# UTS_RaceCounter.net
KiCad netlist of a schematic drawn in EAGLE
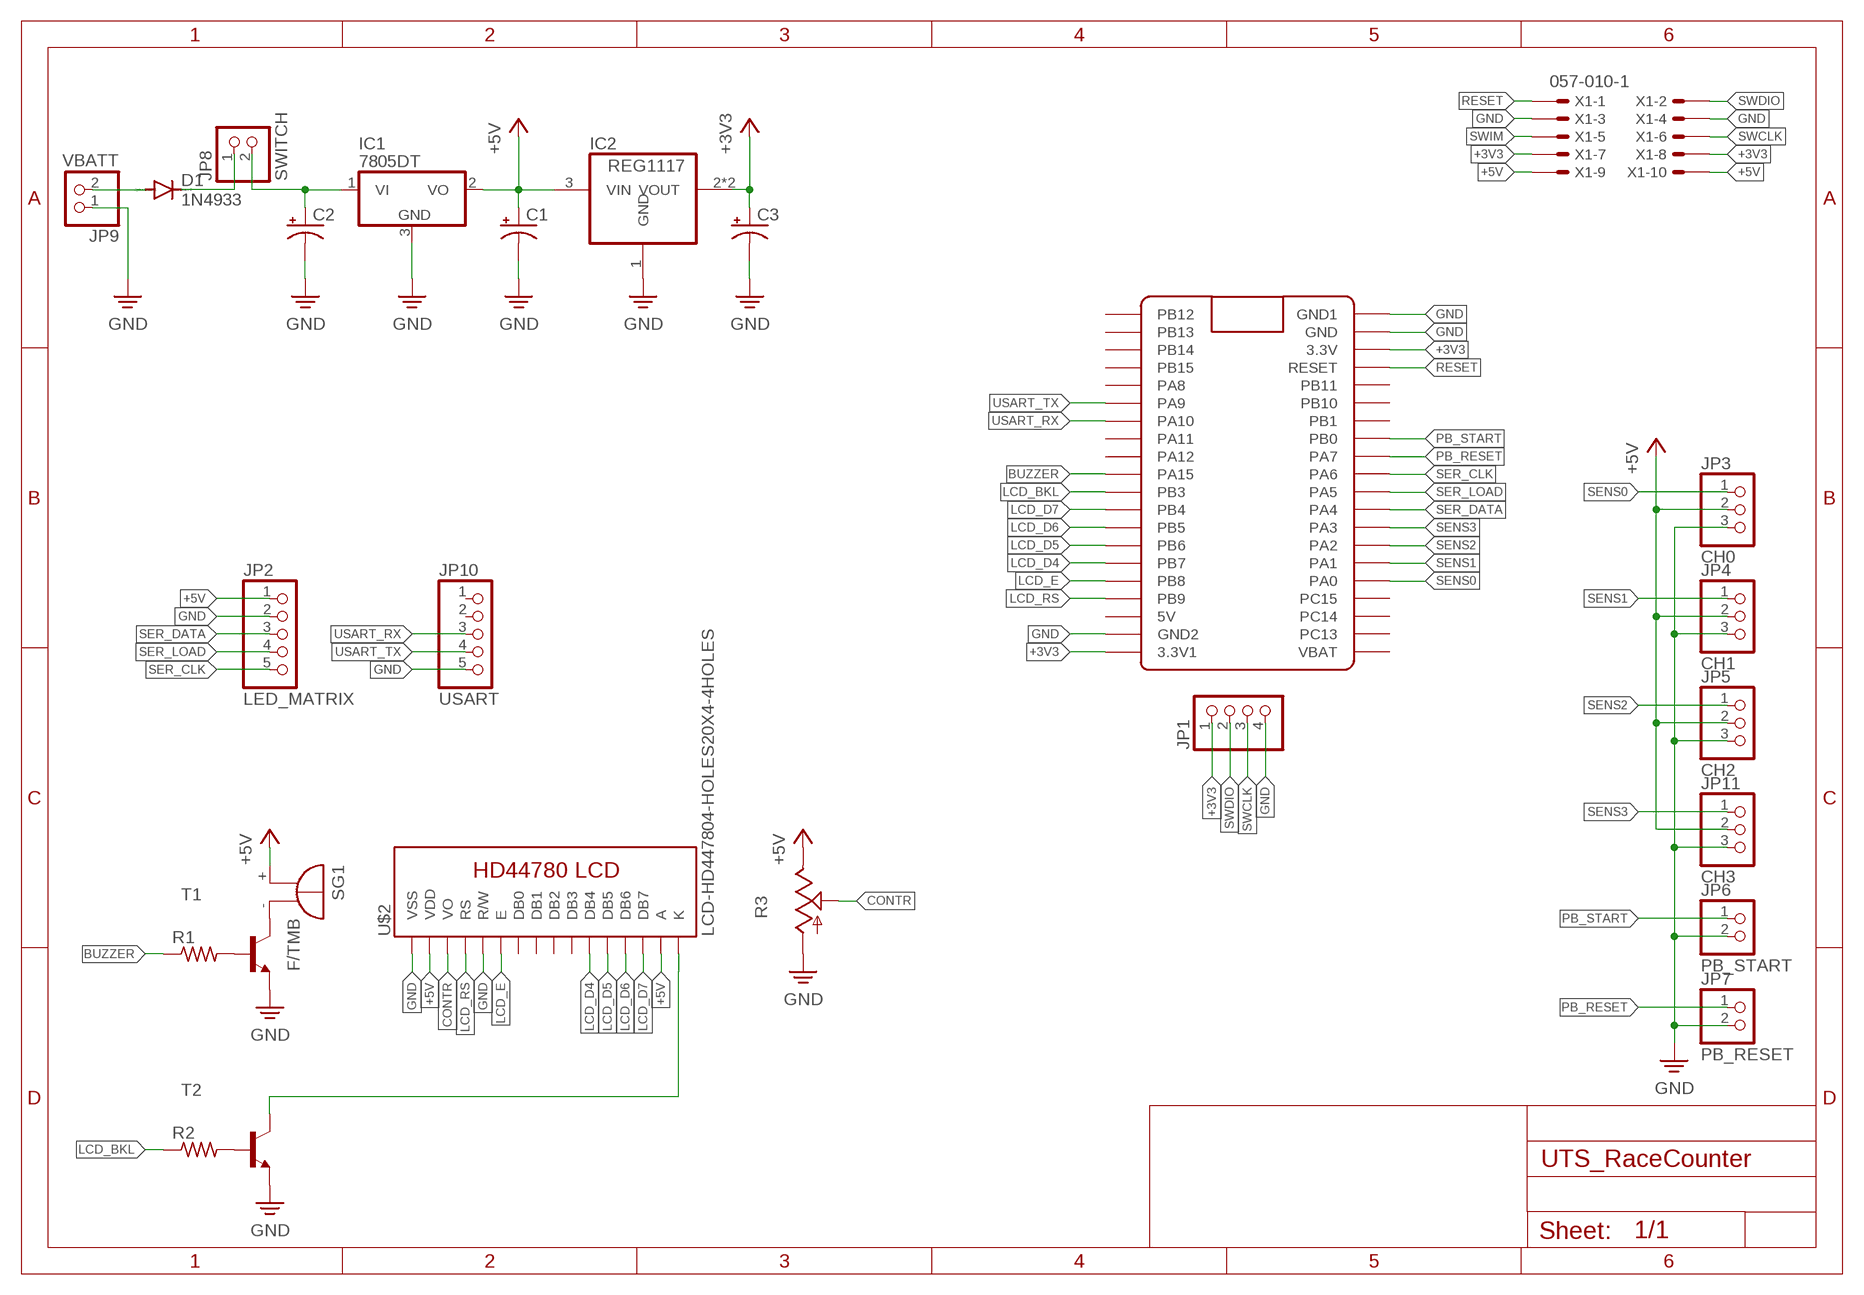
[diagram p0: schematic, sheet 1]

(export (version "E")
  (design (tool "Eeschema 10.0.6"))
  (components
    (comp (ref "C1")
      (value "CPOL-USE2.5-6")
      (footprint "eagle-import:E2,5-6")
      (libsource (lib "eagle-import") (part "CPOL-USE2.5-6"))
    )
    (comp (ref "C2")
      (value "CPOL-USE2.5-6")
      (footprint "eagle-import:E2,5-6")
      (libsource (lib "eagle-import") (part "CPOL-USE2.5-6"))
    )
    (comp (ref "C3")
      (value "CPOL-USE2.5-6")
      (footprint "eagle-import:E2,5-6")
      (libsource (lib "eagle-import") (part "CPOL-USE2.5-6"))
    )
    (comp (ref "D1")
      (value "1N4933")
      (footprint "eagle-import:DO41-10")
      (libsource (lib "eagle-import") (part "1N4933"))
    )
    (comp (ref "IC1")
      (value "7805DT")
      (footprint "eagle-import:TO252")
      (libsource (lib "eagle-import") (part "78DT05"))
    )
    (comp (ref "IC2")
      (value "REG1117")
      (footprint "eagle-import:SOT223")
      (libsource (lib "eagle-import") (part "REG1117"))
    )
    (comp (ref "JP1")
      (value "PINHD-1X4")
      (footprint "eagle-import:1X04")
      (libsource (lib "eagle-import") (part "PINHD-1X4"))
    )
    (comp (ref "JP2")
      (value "LED_MATRIX")
      (footprint "eagle-import:1X05")
      (libsource (lib "eagle-import") (part "PINHD-1X5"))
    )
    (comp (ref "JP3")
      (value "CH0")
      (footprint "eagle-import:1X03")
      (libsource (lib "eagle-import") (part "PINHD-1X3"))
    )
    (comp (ref "JP4")
      (value "CH1")
      (footprint "eagle-import:1X03")
      (libsource (lib "eagle-import") (part "PINHD-1X3"))
    )
    (comp (ref "JP5")
      (value "CH2")
      (footprint "eagle-import:1X03")
      (libsource (lib "eagle-import") (part "PINHD-1X3"))
    )
    (comp (ref "JP6")
      (value "PB_START")
      (footprint "eagle-import:1X02")
      (libsource (lib "eagle-import") (part "PINHD-1X2"))
    )
    (comp (ref "JP7")
      (value "PB_RESET")
      (footprint "eagle-import:1X02")
      (libsource (lib "eagle-import") (part "PINHD-1X2"))
    )
    (comp (ref "JP8")
      (value "SWITCH")
      (footprint "eagle-import:1X02")
      (libsource (lib "eagle-import") (part "PINHD-1X2"))
    )
    (comp (ref "JP9")
      (value "VBATT")
      (footprint "eagle-import:1X02")
      (libsource (lib "eagle-import") (part "PINHD-1X2"))
    )
    (comp (ref "JP10")
      (value "USART")
      (footprint "eagle-import:1X05")
      (libsource (lib "eagle-import") (part "PINHD-1X5"))
    )
    (comp (ref "JP11")
      (value "CH3")
      (footprint "eagle-import:1X03")
      (libsource (lib "eagle-import") (part "PINHD-1X3"))
    )
    (comp (ref "R1")
      (value "R-US_0204/7")
      (footprint "eagle-import:0204_7")
      (libsource (lib "eagle-import") (part "R-US_0204/7"))
    )
    (comp (ref "R2")
      (value "R-US_0204/7")
      (footprint "eagle-import:0204_7")
      (libsource (lib "eagle-import") (part "R-US_0204/7"))
    )
    (comp (ref "R3")
      (value "TRIM_US-CA6V")
      (footprint "eagle-import:CA6V")
      (libsource (lib "eagle-import") (part "TRIM_US-CA6V"))
    )
    (comp (ref "SG1")
      (value "F/TMB")
      (footprint "eagle-import:F_TMB")
      (libsource (lib "eagle-import") (part "F/TMB"))
    )
    (comp (ref "T1")
      (value "BC167-NPN-TO92-ECB")
      (footprint "eagle-import:TO92-ECB")
      (libsource (lib "eagle-import") (part "-NPN-TO92-ECBBC167"))
    )
    (comp (ref "T2")
      (value "BC167-NPN-TO92-ECB")
      (footprint "eagle-import:TO92-ECB")
      (libsource (lib "eagle-import") (part "-NPN-TO92-ECBBC167"))
    )
    (comp (ref "U$1")
      (value "BLUE_PILL")
      (footprint "eagle-import:BLUE_PILL")
      (libsource (lib "eagle-import") (part "BLUE_PILL"))
    )
    (comp (ref "U$2")
      (value "LCD-HD447804-HOLES20X4-4HOLES")
      (footprint "eagle-import:LCD-20X4-4HOLES")
      (libsource (lib "eagle-import") (part "LCD-HD4478020X4-4HOLES4-HOLES"))
    )
    (comp (ref "X1")
      (value "057-010-1")
      (footprint "eagle-import:057-010-1")
      (libsource (lib "eagle-import") (part "057-010-1"))
    )
  )
  (nets
    (net (code "1") (name "+3V3") (class "Default")
      (node (ref "C3") (pin "+") (pinfunction "+_+") (pintype "passive"))
      (node (ref "IC2") (pin "2") (pinfunction "VOUT_2") (pintype "output"))
      (node (ref "IC2") (pin "4") (pinfunction "VOUT_4") (pintype "output"))
      (node (ref "JP1") (pin "1") (pinfunction "1_1") (pintype "passive"))
      (node (ref "U$1") (pin "P$20") (pinfunction "3.3V1_P$20") (pintype "bidirectional"))
      (node (ref "U$1") (pin "P$23") (pinfunction "3.3V_P$23") (pintype "bidirectional"))
      (node (ref "X1") (pin "7") (pinfunction "S_7") (pintype "passive"))
      (node (ref "X1") (pin "8") (pinfunction "S_8") (pintype "passive"))
    )
    (net (code "2") (name "+5V") (class "Default")
      (node (ref "C1") (pin "+") (pinfunction "+_+") (pintype "passive"))
      (node (ref "IC1") (pin "2") (pinfunction "VO_2") (pintype "passive"))
      (node (ref "IC2") (pin "3") (pinfunction "VIN_3") (pintype "input"))
      (node (ref "JP11") (pin "2") (pinfunction "2_2") (pintype "passive"))
      (node (ref "JP2") (pin "1") (pinfunction "1_1") (pintype "passive"))
      (node (ref "JP3") (pin "2") (pinfunction "2_2") (pintype "passive"))
      (node (ref "JP4") (pin "2") (pinfunction "2_2") (pintype "passive"))
      (node (ref "JP5") (pin "2") (pinfunction "2_2") (pintype "passive"))
      (node (ref "R3") (pin "E") (pinfunction "E_E") (pintype "passive"))
      (node (ref "SG1") (pin "+") (pinfunction "+_+") (pintype "passive"))
      (node (ref "U$2") (pin "P$15") (pinfunction "A_P$15") (pintype "power_in"))
      (node (ref "U$2") (pin "P$2") (pinfunction "VDD_P$2") (pintype "power_in"))
      (node (ref "X1") (pin "10") (pinfunction "S_10") (pintype "passive"))
      (node (ref "X1") (pin "9") (pinfunction "S_9") (pintype "passive"))
    )
    (net (code "3") (name "BUZZER") (class "Default")
      (node (ref "R1") (pin "1") (pinfunction "1_1") (pintype "passive"))
      (node (ref "U$1") (pin "P$10") (pinfunction "PA15_P$10") (pintype "bidirectional"))
    )
    (net (code "4") (name "CONTR") (class "Default")
      (node (ref "R3") (pin "S") (pinfunction "S_S") (pintype "passive"))
      (node (ref "U$2") (pin "P$3") (pinfunction "VO_P$3") (pintype "bidirectional"))
    )
    (net (code "5") (name "GND") (class "Default")
      (node (ref "C1") (pin "-") (pinfunction "-_-") (pintype "passive"))
      (node (ref "C2") (pin "-") (pinfunction "-_-") (pintype "passive"))
      (node (ref "C3") (pin "-") (pinfunction "-_-") (pintype "passive"))
      (node (ref "IC1") (pin "3") (pinfunction "GND_3") (pintype "passive"))
      (node (ref "IC2") (pin "1") (pinfunction "GND_1") (pintype "power_in"))
      (node (ref "JP1") (pin "4") (pinfunction "4_4") (pintype "passive"))
      (node (ref "JP10") (pin "5") (pinfunction "5_5") (pintype "passive"))
      (node (ref "JP11") (pin "3") (pinfunction "3_3") (pintype "passive"))
      (node (ref "JP2") (pin "2") (pinfunction "2_2") (pintype "passive"))
      (node (ref "JP3") (pin "3") (pinfunction "3_3") (pintype "passive"))
      (node (ref "JP4") (pin "3") (pinfunction "3_3") (pintype "passive"))
      (node (ref "JP5") (pin "3") (pinfunction "3_3") (pintype "passive"))
      (node (ref "JP6") (pin "2") (pinfunction "2_2") (pintype "passive"))
      (node (ref "JP7") (pin "2") (pinfunction "2_2") (pintype "passive"))
      (node (ref "JP9") (pin "1") (pinfunction "1_1") (pintype "passive"))
      (node (ref "R3") (pin "A") (pinfunction "A_A") (pintype "passive"))
      (node (ref "T1") (pin "E") (pinfunction "E_E") (pintype "passive"))
      (node (ref "T2") (pin "E") (pinfunction "E_E") (pintype "passive"))
      (node (ref "U$1") (pin "P$19") (pinfunction "GND2_P$19") (pintype "bidirectional"))
      (node (ref "U$1") (pin "P$21") (pinfunction "GND1_P$21") (pintype "power_in"))
      (node (ref "U$1") (pin "P$22") (pinfunction "GND_P$22") (pintype "bidirectional"))
      (node (ref "U$2") (pin "P$1") (pinfunction "VSS_P$1") (pintype "power_in"))
      (node (ref "U$2") (pin "P$5") (pinfunction "R/W_P$5") (pintype "input"))
      (node (ref "X1") (pin "3") (pinfunction "S_3") (pintype "passive"))
      (node (ref "X1") (pin "4") (pinfunction "S_4") (pintype "passive"))
    )
    (net (code "6") (name "LCD_BKL") (class "Default")
      (node (ref "R2") (pin "1") (pinfunction "1_1") (pintype "passive"))
      (node (ref "U$1") (pin "P$11") (pinfunction "PB3_P$11") (pintype "bidirectional"))
    )
    (net (code "7") (name "LCD_D4") (class "Default")
      (node (ref "U$1") (pin "P$15") (pinfunction "PB7_P$15") (pintype "bidirectional"))
      (node (ref "U$2") (pin "P$11") (pinfunction "DB4_P$11") (pintype "bidirectional"))
    )
    (net (code "8") (name "LCD_D5") (class "Default")
      (node (ref "U$1") (pin "P$14") (pinfunction "PB6_P$14") (pintype "bidirectional"))
      (node (ref "U$2") (pin "P$12") (pinfunction "DB5_P$12") (pintype "bidirectional"))
    )
    (net (code "9") (name "LCD_D6") (class "Default")
      (node (ref "U$1") (pin "P$13") (pinfunction "PB5_P$13") (pintype "bidirectional"))
      (node (ref "U$2") (pin "P$13") (pinfunction "DB6_P$13") (pintype "bidirectional"))
    )
    (net (code "10") (name "LCD_D7") (class "Default")
      (node (ref "U$1") (pin "P$12") (pinfunction "PB4_P$12") (pintype "bidirectional"))
      (node (ref "U$2") (pin "P$14") (pinfunction "DB7_P$14") (pintype "bidirectional"))
    )
    (net (code "11") (name "LCD_E") (class "Default")
      (node (ref "U$1") (pin "P$16") (pinfunction "PB8_P$16") (pintype "bidirectional"))
      (node (ref "U$2") (pin "P$6") (pinfunction "E_P$6") (pintype "input"))
    )
    (net (code "12") (name "LCD_RS") (class "Default")
      (node (ref "U$1") (pin "P$17") (pinfunction "PB9_P$17") (pintype "bidirectional"))
      (node (ref "U$2") (pin "P$4") (pinfunction "RS_P$4") (pintype "input"))
    )
    (net (code "13") (name "Net-(D1-PadA)") (class "Default")
      (node (ref "D1") (pin "A") (pinfunction "A_A") (pintype "passive"))
      (node (ref "JP9") (pin "2") (pinfunction "2_2") (pintype "passive"))
    )
    (net (code "14") (name "Net-(D1-PadC)") (class "Default")
      (node (ref "D1") (pin "C") (pinfunction "C_C") (pintype "passive"))
      (node (ref "JP8") (pin "1") (pinfunction "1_1") (pintype "passive"))
    )
    (net (code "15") (name "Net-(IC1-VI)") (class "Default")
      (node (ref "C2") (pin "+") (pinfunction "+_+") (pintype "passive"))
      (node (ref "IC1") (pin "1") (pinfunction "VI_1") (pintype "input"))
      (node (ref "JP8") (pin "2") (pinfunction "2_2") (pintype "passive"))
    )
    (net (code "16") (name "Net-(R1-Pad2)") (class "Default")
      (node (ref "R1") (pin "2") (pinfunction "2_2") (pintype "passive"))
      (node (ref "T1") (pin "B") (pinfunction "B_B") (pintype "passive"))
    )
    (net (code "17") (name "Net-(R2-Pad2)") (class "Default")
      (node (ref "R2") (pin "2") (pinfunction "2_2") (pintype "passive"))
      (node (ref "T2") (pin "B") (pinfunction "B_B") (pintype "passive"))
    )
    (net (code "18") (name "Net-(SG1-Pad-)") (class "Default")
      (node (ref "SG1") (pin "-") (pinfunction "-_-") (pintype "passive"))
      (node (ref "T1") (pin "C") (pinfunction "C_C") (pintype "passive"))
    )
    (net (code "19") (name "Net-(U$2-K)") (class "Default")
      (node (ref "T2") (pin "C") (pinfunction "C_C") (pintype "passive"))
      (node (ref "U$2") (pin "P$16") (pinfunction "K_P$16") (pintype "power_in"))
    )
    (net (code "20") (name "PB_RESET") (class "Default")
      (node (ref "JP7") (pin "1") (pinfunction "1_1") (pintype "passive"))
      (node (ref "U$1") (pin "P$29") (pinfunction "PA7_P$29") (pintype "bidirectional"))
    )
    (net (code "21") (name "PB_START") (class "Default")
      (node (ref "JP6") (pin "1") (pinfunction "1_1") (pintype "passive"))
      (node (ref "U$1") (pin "P$28") (pinfunction "PB0_P$28") (pintype "bidirectional"))
    )
    (net (code "22") (name "RESET") (class "Default")
      (node (ref "U$1") (pin "P$24") (pinfunction "RESET_P$24") (pintype "bidirectional"))
      (node (ref "X1") (pin "1") (pinfunction "S_1") (pintype "passive"))
    )
    (net (code "23") (name "SENS0") (class "Default")
      (node (ref "JP3") (pin "1") (pinfunction "1_1") (pintype "passive"))
      (node (ref "U$1") (pin "P$36") (pinfunction "PA0_P$36") (pintype "bidirectional"))
    )
    (net (code "24") (name "SENS1") (class "Default")
      (node (ref "JP4") (pin "1") (pinfunction "1_1") (pintype "passive"))
      (node (ref "U$1") (pin "P$35") (pinfunction "PA1_P$35") (pintype "bidirectional"))
    )
    (net (code "25") (name "SENS2") (class "Default")
      (node (ref "JP5") (pin "1") (pinfunction "1_1") (pintype "passive"))
      (node (ref "U$1") (pin "P$34") (pinfunction "PA2_P$34") (pintype "bidirectional"))
    )
    (net (code "26") (name "SENS3") (class "Default")
      (node (ref "JP11") (pin "1") (pinfunction "1_1") (pintype "passive"))
      (node (ref "U$1") (pin "P$33") (pinfunction "PA3_P$33") (pintype "bidirectional"))
    )
    (net (code "27") (name "SER_CLK") (class "Default")
      (node (ref "JP2") (pin "5") (pinfunction "5_5") (pintype "passive"))
      (node (ref "U$1") (pin "P$30") (pinfunction "PA6_P$30") (pintype "bidirectional"))
    )
    (net (code "28") (name "SER_DATA") (class "Default")
      (node (ref "JP2") (pin "3") (pinfunction "3_3") (pintype "passive"))
      (node (ref "U$1") (pin "P$32") (pinfunction "PA4_P$32") (pintype "bidirectional"))
    )
    (net (code "29") (name "SER_LOAD") (class "Default")
      (node (ref "JP2") (pin "4") (pinfunction "4_4") (pintype "passive"))
      (node (ref "U$1") (pin "P$31") (pinfunction "PA5_P$31") (pintype "bidirectional"))
    )
    (net (code "30") (name "SWCLK") (class "Default")
      (node (ref "JP1") (pin "3") (pinfunction "3_3") (pintype "passive"))
      (node (ref "X1") (pin "6") (pinfunction "S_6") (pintype "passive"))
    )
    (net (code "31") (name "SWDIO") (class "Default")
      (node (ref "JP1") (pin "2") (pinfunction "2_2") (pintype "passive"))
      (node (ref "X1") (pin "2") (pinfunction "S_2") (pintype "passive"))
    )
    (net (code "32") (name "SWIM") (class "Default")
      (node (ref "X1") (pin "5") (pinfunction "S_5") (pintype "passive"))
    )
    (net (code "33") (name "USART_RX") (class "Default")
      (node (ref "JP10") (pin "3") (pinfunction "3_3") (pintype "passive"))
      (node (ref "U$1") (pin "P$7") (pinfunction "PA10_P$7") (pintype "bidirectional"))
    )
    (net (code "34") (name "USART_TX") (class "Default")
      (node (ref "JP10") (pin "4") (pinfunction "4_4") (pintype "passive"))
      (node (ref "U$1") (pin "P$6") (pinfunction "PA9_P$6") (pintype "bidirectional"))
    )
    (net (code "35") (name "unconnected-(JP10-Pad1)") (class "Default")
      (node (ref "JP10") (pin "1") (pinfunction "1_1") (pintype "passive"))
    )
    (net (code "36") (name "unconnected-(JP10-Pad2)") (class "Default")
      (node (ref "JP10") (pin "2") (pinfunction "2_2") (pintype "passive"))
    )
    (net (code "37") (name "unconnected-(U$1-5V-PadP$18)") (class "Default")
      (node (ref "U$1") (pin "P$18") (pinfunction "5V_P$18") (pintype "bidirectional"))
    )
    (net (code "38") (name "unconnected-(U$1-PA8-PadP$5)") (class "Default")
      (node (ref "U$1") (pin "P$5") (pinfunction "PA8_P$5") (pintype "bidirectional"))
    )
    (net (code "39") (name "unconnected-(U$1-PA11-PadP$8)") (class "Default")
      (node (ref "U$1") (pin "P$8") (pinfunction "PA11_P$8") (pintype "bidirectional"))
    )
    (net (code "40") (name "unconnected-(U$1-PA12-PadP$9)") (class "Default")
      (node (ref "U$1") (pin "P$9") (pinfunction "PA12_P$9") (pintype "bidirectional"))
    )
    (net (code "41") (name "unconnected-(U$1-PB1-PadP$27)") (class "Default")
      (node (ref "U$1") (pin "P$27") (pinfunction "PB1_P$27") (pintype "bidirectional"))
    )
    (net (code "42") (name "unconnected-(U$1-PB10-PadP$26)") (class "Default")
      (node (ref "U$1") (pin "P$26") (pinfunction "PB10_P$26") (pintype "bidirectional"))
    )
    (net (code "43") (name "unconnected-(U$1-PB11-PadP$25)") (class "Default")
      (node (ref "U$1") (pin "P$25") (pinfunction "PB11_P$25") (pintype "bidirectional"))
    )
    (net (code "44") (name "unconnected-(U$1-PB12-PadP$1)") (class "Default")
      (node (ref "U$1") (pin "P$1") (pinfunction "PB12_P$1") (pintype "bidirectional"))
    )
    (net (code "45") (name "unconnected-(U$1-PB13-PadP$2)") (class "Default")
      (node (ref "U$1") (pin "P$2") (pinfunction "PB13_P$2") (pintype "bidirectional"))
    )
    (net (code "46") (name "unconnected-(U$1-PB14-PadP$3)") (class "Default")
      (node (ref "U$1") (pin "P$3") (pinfunction "PB14_P$3") (pintype "bidirectional"))
    )
    (net (code "47") (name "unconnected-(U$1-PB15-PadP$4)") (class "Default")
      (node (ref "U$1") (pin "P$4") (pinfunction "PB15_P$4") (pintype "bidirectional"))
    )
    (net (code "48") (name "unconnected-(U$1-PC13-PadP$39)") (class "Default")
      (node (ref "U$1") (pin "P$39") (pinfunction "PC13_P$39") (pintype "bidirectional"))
    )
    (net (code "49") (name "unconnected-(U$1-PC14-PadP$38)") (class "Default")
      (node (ref "U$1") (pin "P$38") (pinfunction "PC14_P$38") (pintype "bidirectional"))
    )
    (net (code "50") (name "unconnected-(U$1-PC15-PadP$37)") (class "Default")
      (node (ref "U$1") (pin "P$37") (pinfunction "PC15_P$37") (pintype "bidirectional"))
    )
    (net (code "51") (name "unconnected-(U$1-VBAT-PadP$40)") (class "Default")
      (node (ref "U$1") (pin "P$40") (pinfunction "VBAT_P$40") (pintype "bidirectional"))
    )
    (net (code "52") (name "unconnected-(U$2-DB0-PadP$7)") (class "Default")
      (node (ref "U$2") (pin "P$7") (pinfunction "DB0_P$7") (pintype "bidirectional"))
    )
    (net (code "53") (name "unconnected-(U$2-DB1-PadP$8)") (class "Default")
      (node (ref "U$2") (pin "P$8") (pinfunction "DB1_P$8") (pintype "bidirectional"))
    )
    (net (code "54") (name "unconnected-(U$2-DB2-PadP$9)") (class "Default")
      (node (ref "U$2") (pin "P$9") (pinfunction "DB2_P$9") (pintype "bidirectional"))
    )
    (net (code "55") (name "unconnected-(U$2-DB3-PadP$10)") (class "Default")
      (node (ref "U$2") (pin "P$10") (pinfunction "DB3_P$10") (pintype "bidirectional"))
    )
  )
)
